# Main_ESP32.net
KiCad netlist of a schematic drawn in EAGLE
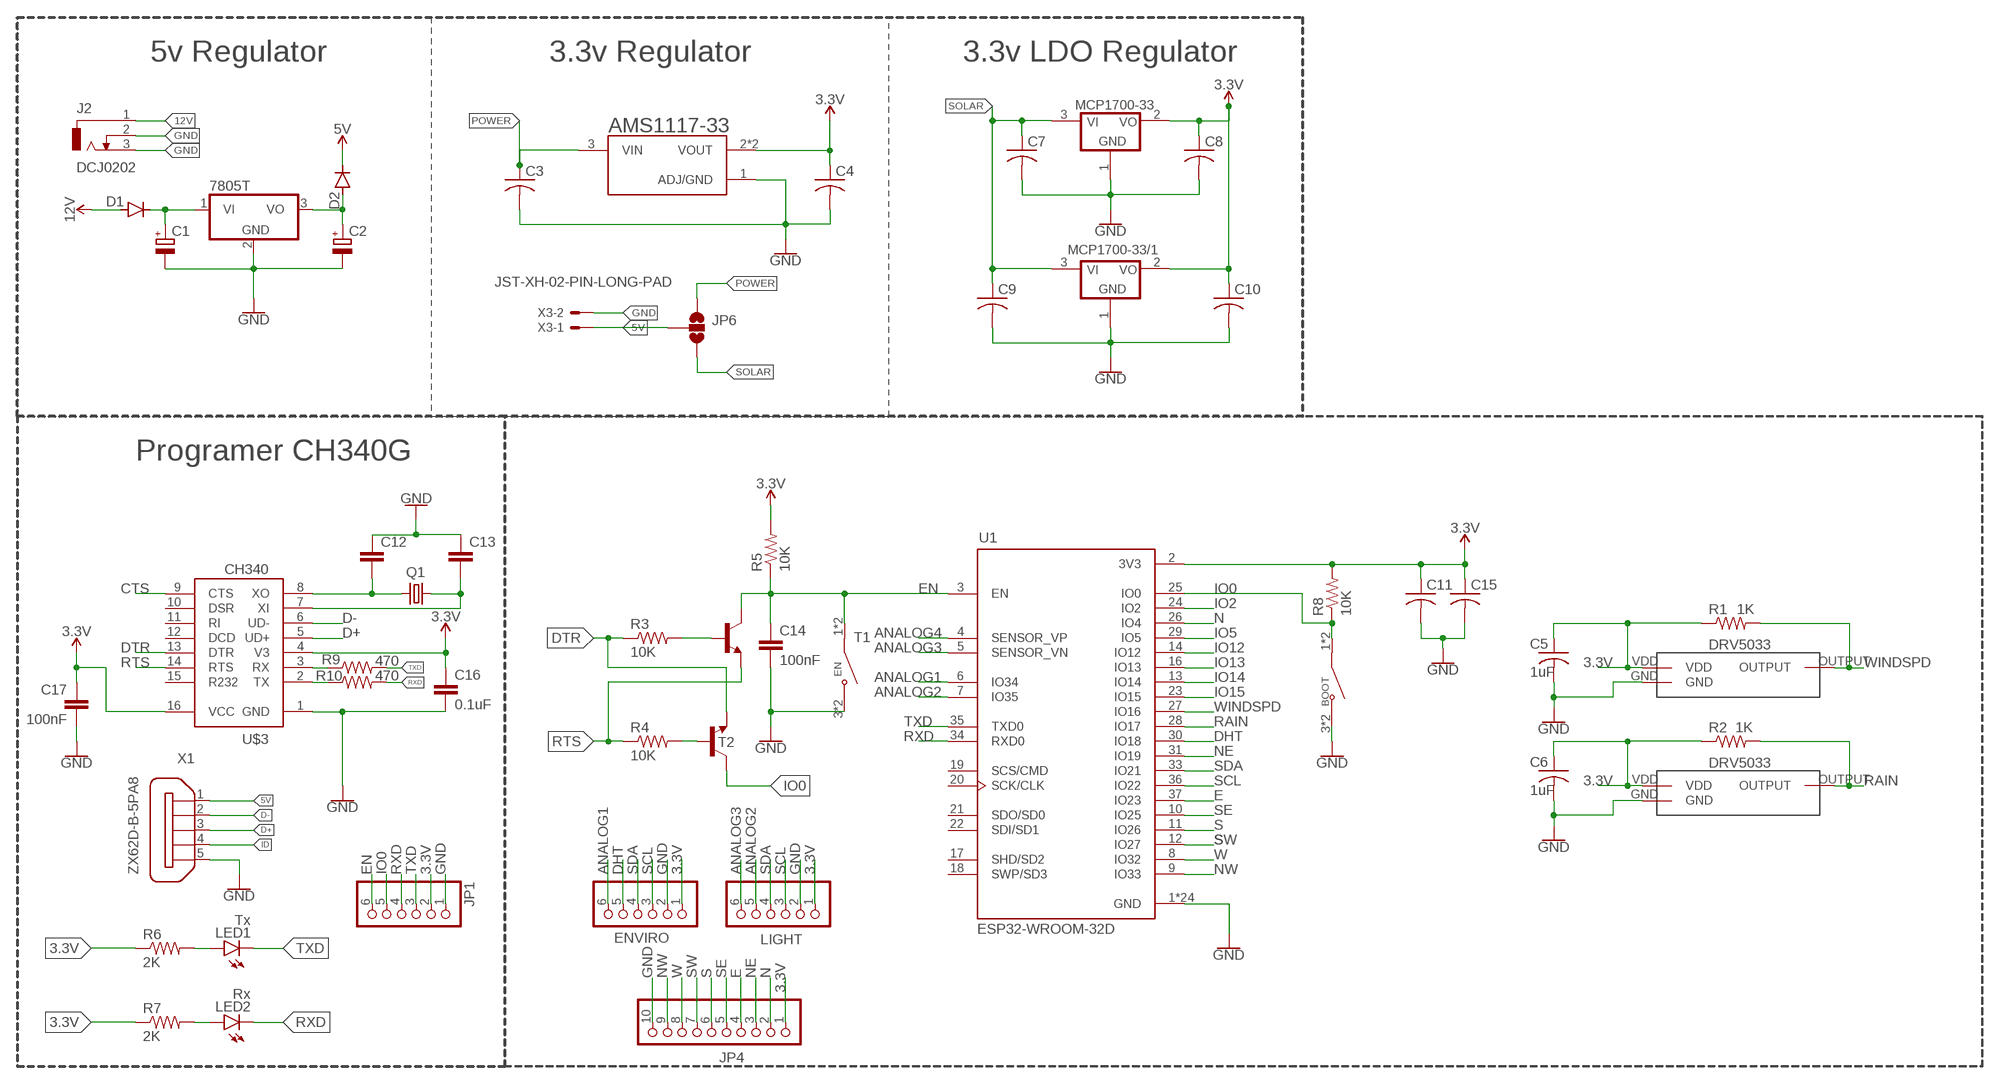
[diagram p0: schematic, sheet 1]

(export (version "E")
  (design (tool "Eeschema 10.0.6"))
  (components
    (comp (ref "AMS1117-33")
      (value "AMS1117-5.0")
      (footprint "eagle-import:SOT229P700X180-4N")
      (fields (field (name "MF") "Advanced Monolithic Systems"))
      (libsource (lib "eagle-import") (part "AMS1117-5.0"))
    )
    (comp (ref "BOOT")
      (value "2-1437565-9")
      (footprint "eagle-import:SW_2-1437565-9")
      (fields (field (name "MF") "TE Connectivity"))
      (libsource (lib "eagle-import") (part "2-1437565-9"))
    )
    (comp (ref "C1")
      (value "CPOL-EUE2.5-5")
      (footprint "eagle-import:E2,5-5")
      (libsource (lib "eagle-import") (part "CPOL-EUE2.5-5"))
    )
    (comp (ref "C2")
      (value "CPOL-EUE2.5-5")
      (footprint "eagle-import:E2,5-5")
      (libsource (lib "eagle-import") (part "CPOL-EUE2.5-5"))
    )
    (comp (ref "C3")
      (value "C-USC1206K")
      (footprint "eagle-import:C1206K")
      (libsource (lib "eagle-import") (part "C-USC1206K"))
    )
    (comp (ref "C4")
      (value "C-USC1206K")
      (footprint "eagle-import:C1206K")
      (libsource (lib "eagle-import") (part "C-USC1206K"))
    )
    (comp (ref "C5")
      (value "1uF")
      (footprint "eagle-import:C1206K")
      (libsource (lib "eagle-import") (part "C-USC1206K"))
    )
    (comp (ref "C6")
      (value "1uF")
      (footprint "eagle-import:C1206K")
      (libsource (lib "eagle-import") (part "C-USC1206K"))
    )
    (comp (ref "C7")
      (value "C-USC1206K")
      (footprint "eagle-import:C1206K")
      (libsource (lib "eagle-import") (part "C-USC1206K"))
    )
    (comp (ref "C8")
      (value "C-USC1206K")
      (footprint "eagle-import:C1206K")
      (libsource (lib "eagle-import") (part "C-USC1206K"))
    )
    (comp (ref "C9")
      (value "C-USC1206K")
      (footprint "eagle-import:C1206K")
      (libsource (lib "eagle-import") (part "C-USC1206K"))
    )
    (comp (ref "C10")
      (value "C-USC1206K")
      (footprint "eagle-import:C1206K")
      (libsource (lib "eagle-import") (part "C-USC1206K"))
    )
    (comp (ref "C11")
      (value "C-USC1206K")
      (footprint "eagle-import:C1206K")
      (libsource (lib "eagle-import") (part "C-USC1206K"))
    )
    (comp (ref "C12")
      (value "C-EUC1206K")
      (footprint "eagle-import:C1206K")
      (libsource (lib "eagle-import") (part "C-EUC1206K"))
    )
    (comp (ref "C13")
      (value "C-EUC1206K")
      (footprint "eagle-import:C1206K")
      (libsource (lib "eagle-import") (part "C-EUC1206K"))
    )
    (comp (ref "C14")
      (value "100nF")
      (footprint "eagle-import:C1206K")
      (libsource (lib "eagle-import") (part "C-EUC1206K"))
    )
    (comp (ref "C15")
      (value "C-USC1206K")
      (footprint "eagle-import:C1206K")
      (libsource (lib "eagle-import") (part "C-USC1206K"))
    )
    (comp (ref "C16")
      (value "0.1uF")
      (footprint "eagle-import:C1206K")
      (libsource (lib "eagle-import") (part "C-EUC1206K"))
    )
    (comp (ref "C17")
      (value "100nF")
      (footprint "eagle-import:C1206K")
      (libsource (lib "eagle-import") (part "C-EUC1206K"))
    )
    (comp (ref "D1")
      (value "1N4148DO35-10")
      (footprint "eagle-import:DO35-10")
      (libsource (lib "eagle-import") (part "1N4148DO35-10"))
    )
    (comp (ref "D2")
      (value "1N4148DO35-10")
      (footprint "eagle-import:DO35-10")
      (libsource (lib "eagle-import") (part "1N4148DO35-10"))
    )
    (comp (ref "EN")
      (value "2-1437565-9")
      (footprint "eagle-import:SW_2-1437565-9")
      (fields (field (name "MF") "TE Connectivity"))
      (libsource (lib "eagle-import") (part "2-1437565-9"))
    )
    (comp (ref "ENVIRO")
      (value "PINHD-1X6/90")
      (footprint "eagle-import:1X06_90")
      (libsource (lib "eagle-import") (part "PINHD-1X6/90"))
    )
    (comp (ref "IC1")
      (value "7805T")
      (footprint "eagle-import:TO220H")
      (libsource (lib "eagle-import") (part "78T05"))
    )
    (comp (ref "J2")
      (value "DCJ0202")
      (footprint "eagle-import:DCJ0202")
      (libsource (lib "eagle-import") (part "DCJ0202"))
    )
    (comp (ref "JP1")
      (value "PINHD-1X6")
      (footprint "eagle-import:1X06")
      (libsource (lib "eagle-import") (part "PINHD-1X6"))
    )
    (comp (ref "JP4")
      (value "PINHD-1X10/90")
      (footprint "eagle-import:1X10_90")
      (libsource (lib "eagle-import") (part "PINHD-1X10/90"))
    )
    (comp (ref "JP6")
      (value "JUMPER-SMT_3_NO_SILK")
      (footprint "eagle-import:SMT-JUMPER_3_NO_SILK")
      (libsource (lib "eagle-import") (part "JUMPER-SMT_3_NO_SILK"))
    )
    (comp (ref "LED1")
      (value "Tx")
      (footprint "eagle-import:CHIPLED_1206")
      (libsource (lib "eagle-import") (part "LEDCHIPLED_1206"))
    )
    (comp (ref "LED2")
      (value "Rx")
      (footprint "eagle-import:CHIPLED_1206")
      (libsource (lib "eagle-import") (part "LEDCHIPLED_1206"))
    )
    (comp (ref "LIGHT")
      (value "Light")
      (footprint "eagle-import:1X06_90")
      (libsource (lib "eagle-import") (part "PINHD-1X6/90"))
    )
    (comp (ref "MCP1700-33")
      (value "MCP1703-3302E/CB")
      (footprint "eagle-import:SOT23A_MICROCHIP_CB")
      (libsource (lib "eagle-import") (part "MCP170302E/CB-33"))
    )
    (comp (ref "MCP1700-33/1")
      (value "MCP1703-3302E/CB")
      (footprint "eagle-import:SOT23A_MICROCHIP_CB")
      (libsource (lib "eagle-import") (part "MCP170302E/CB-33"))
    )
    (comp (ref "Q1")
      (value "CRYSTALHC49S")
      (footprint "eagle-import:HC49_S")
      (libsource (lib "eagle-import") (part "CRYSTALHC49S"))
    )
    (comp (ref "R1")
      (value "1K")
      (footprint "eagle-import:R1206")
      (libsource (lib "eagle-import") (part "R-US_R1206"))
    )
    (comp (ref "R2")
      (value "1K")
      (footprint "eagle-import:R1206")
      (libsource (lib "eagle-import") (part "R-US_R1206"))
    )
    (comp (ref "R3")
      (value "10K")
      (footprint "eagle-import:R1206")
      (libsource (lib "eagle-import") (part "R-US_R1206"))
    )
    (comp (ref "R4")
      (value "10K")
      (footprint "eagle-import:R1206")
      (libsource (lib "eagle-import") (part "R-US_R1206"))
    )
    (comp (ref "R5")
      (value "10K")
      (footprint "eagle-import:R1206")
      (libsource (lib "eagle-import") (part "R-US_R1206"))
    )
    (comp (ref "R6")
      (value "2K")
      (footprint "eagle-import:R1206")
      (libsource (lib "eagle-import") (part "R-US_R1206"))
    )
    (comp (ref "R7")
      (value "2K")
      (footprint "eagle-import:R1206")
      (libsource (lib "eagle-import") (part "R-US_R1206"))
    )
    (comp (ref "R8")
      (value "10K")
      (footprint "eagle-import:R1206")
      (libsource (lib "eagle-import") (part "R-US_R1206"))
    )
    (comp (ref "R9")
      (value "470")
      (footprint "eagle-import:R1206")
      (libsource (lib "eagle-import") (part "R-US_R1206"))
    )
    (comp (ref "R10")
      (value "470")
      (footprint "eagle-import:R1206")
      (libsource (lib "eagle-import") (part "R-US_R1206"))
    )
    (comp (ref "T1")
      (value "BC847")
      (footprint "eagle-import:SOT23")
      (libsource (lib "eagle-import") (part "BC850"))
    )
    (comp (ref "T2")
      (value "BC847")
      (footprint "eagle-import:SOT23")
      (libsource (lib "eagle-import") (part "BC850"))
    )
    (comp (ref "U$1")
      (value "DRV5033")
      (footprint "eagle-import:DRV5033")
      (libsource (lib "eagle-import") (part "DRV5033"))
    )
    (comp (ref "U$2")
      (value "DRV5033")
      (footprint "eagle-import:DRV5033")
      (libsource (lib "eagle-import") (part "DRV5033"))
    )
    (comp (ref "U$3")
      (value "CH340")
      (footprint "eagle-import:SOIC16")
      (fields (field (name "MF") "DFRobot"))
      (libsource (lib "eagle-import") (part "CH340"))
    )
    (comp (ref "U1")
      (value "ESP32-WROOM-32D")
      (footprint "eagle-import:MODULE_ESP32-WROOM-32D")
      (fields (field (name "MF") "Espressif Systems"))
      (libsource (lib "eagle-import") (part "ESP32-WROOM-32D"))
    )
    (comp (ref "X1")
      (value "ZX62D-B-5PA8")
      (footprint "eagle-import:ZX62D-B-5PA8")
      (fields (field (name "MF") "Hirose"))
      (libsource (lib "eagle-import") (part "ZX62D-B-5PA8"))
    )
    (comp (ref "X3")
      (value "JST-XH-02-PIN-LONG-PAD")
      (footprint "eagle-import:JST-XH-02-PACKAGE-LONG-PAD")
      (libsource (lib "eagle-import") (part "JST-XH-02-PIN-LONG-PAD"))
    )
  )
  (nets
    (net (code "1") (name "/ANALOG1") (class "Default")
      (node (ref "ENVIRO") (pin "6") (pinfunction "6_6") (pintype "passive"))
      (node (ref "U1") (pin "6") (pinfunction "IO34_6") (pintype "input"))
    )
    (net (code "2") (name "/ANALOG2") (class "Default")
      (node (ref "LIGHT") (pin "5") (pinfunction "5_5") (pintype "passive"))
      (node (ref "U1") (pin "7") (pinfunction "IO35_7") (pintype "input"))
    )
    (net (code "3") (name "/ANALOG3") (class "Default")
      (node (ref "LIGHT") (pin "6") (pinfunction "6_6") (pintype "passive"))
      (node (ref "U1") (pin "5") (pinfunction "SENSOR_VN_5") (pintype "input"))
    )
    (net (code "4") (name "/ANALOG4") (class "Default")
      (node (ref "U1") (pin "4") (pinfunction "SENSOR_VP_4") (pintype "input"))
    )
    (net (code "5") (name "/CTS") (class "Default")
      (node (ref "U$3") (pin "9") (pinfunction "CTS_9") (pintype "bidirectional"))
    )
    (net (code "6") (name "/DHT") (class "Default")
      (node (ref "ENVIRO") (pin "5") (pinfunction "5_5") (pintype "passive"))
      (node (ref "U1") (pin "30") (pinfunction "IO18_30") (pintype "bidirectional"))
    )
    (net (code "7") (name "/E") (class "Default")
      (node (ref "JP4") (pin "4") (pinfunction "4_4") (pintype "passive"))
      (node (ref "U1") (pin "37") (pinfunction "IO23_37") (pintype "bidirectional"))
    )
    (net (code "8") (name "/EN") (class "Default")
      (node (ref "C14") (pin "1") (pinfunction "1_1") (pintype "passive"))
      (node (ref "EN") (pin "1") (pinfunction "COM_1") (pintype "passive"))
      (node (ref "EN") (pin "2") (pinfunction "COM_2") (pintype "passive"))
      (node (ref "JP1") (pin "6") (pinfunction "6_6") (pintype "passive"))
      (node (ref "R5") (pin "1") (pinfunction "1_1") (pintype "passive"))
      (node (ref "T1") (pin "3") (pinfunction "C_3") (pintype "passive"))
      (node (ref "U1") (pin "3") (pinfunction "EN_3") (pintype "input"))
    )
    (net (code "9") (name "/IO2") (class "Default")
      (node (ref "U1") (pin "24") (pinfunction "IO2_24") (pintype "bidirectional"))
    )
    (net (code "10") (name "/IO5") (class "Default")
      (node (ref "U1") (pin "29") (pinfunction "IO5_29") (pintype "bidirectional"))
    )
    (net (code "11") (name "/IO12") (class "Default")
      (node (ref "U1") (pin "14") (pinfunction "IO12_14") (pintype "bidirectional"))
    )
    (net (code "12") (name "/IO13") (class "Default")
      (node (ref "U1") (pin "16") (pinfunction "IO13_16") (pintype "bidirectional"))
    )
    (net (code "13") (name "/IO14") (class "Default")
      (node (ref "U1") (pin "13") (pinfunction "IO14_13") (pintype "bidirectional"))
    )
    (net (code "14") (name "/IO15") (class "Default")
      (node (ref "U1") (pin "23") (pinfunction "IO15_23") (pintype "bidirectional"))
    )
    (net (code "15") (name "/N") (class "Default")
      (node (ref "JP4") (pin "2") (pinfunction "2_2") (pintype "passive"))
      (node (ref "U1") (pin "26") (pinfunction "IO4_26") (pintype "bidirectional"))
    )
    (net (code "16") (name "/NE") (class "Default")
      (node (ref "JP4") (pin "3") (pinfunction "3_3") (pintype "passive"))
      (node (ref "U1") (pin "31") (pinfunction "IO19_31") (pintype "bidirectional"))
    )
    (net (code "17") (name "/NW") (class "Default")
      (node (ref "JP4") (pin "9") (pinfunction "9_9") (pintype "passive"))
      (node (ref "U1") (pin "9") (pinfunction "IO33_9") (pintype "bidirectional"))
    )
    (net (code "18") (name "/RAIN") (class "Default")
      (node (ref "R2") (pin "2") (pinfunction "2_2") (pintype "passive"))
      (node (ref "U$1") (pin "OUTPUT") (pinfunction "OUTPUT_OUTPUT") (pintype "bidirectional"))
      (node (ref "U1") (pin "28") (pinfunction "IO17_28") (pintype "bidirectional"))
    )
    (net (code "19") (name "/S") (class "Default")
      (node (ref "JP4") (pin "6") (pinfunction "6_6") (pintype "passive"))
      (node (ref "U1") (pin "11") (pinfunction "IO26_11") (pintype "bidirectional"))
    )
    (net (code "20") (name "/SCL") (class "Default")
      (node (ref "ENVIRO") (pin "3") (pinfunction "3_3") (pintype "passive"))
      (node (ref "LIGHT") (pin "3") (pinfunction "3_3") (pintype "passive"))
      (node (ref "U1") (pin "36") (pinfunction "IO22_36") (pintype "bidirectional"))
    )
    (net (code "21") (name "/SDA") (class "Default")
      (node (ref "ENVIRO") (pin "4") (pinfunction "4_4") (pintype "passive"))
      (node (ref "LIGHT") (pin "4") (pinfunction "4_4") (pintype "passive"))
      (node (ref "U1") (pin "33") (pinfunction "IO21_33") (pintype "bidirectional"))
    )
    (net (code "22") (name "/SE") (class "Default")
      (node (ref "JP4") (pin "5") (pinfunction "5_5") (pintype "passive"))
      (node (ref "U1") (pin "10") (pinfunction "IO25_10") (pintype "bidirectional"))
    )
    (net (code "23") (name "/SW") (class "Default")
      (node (ref "JP4") (pin "7") (pinfunction "7_7") (pintype "passive"))
      (node (ref "U1") (pin "12") (pinfunction "IO27_12") (pintype "bidirectional"))
    )
    (net (code "24") (name "/W") (class "Default")
      (node (ref "JP4") (pin "8") (pinfunction "8_8") (pintype "passive"))
      (node (ref "U1") (pin "8") (pinfunction "IO32_8") (pintype "bidirectional"))
    )
    (net (code "25") (name "/WINDSPD") (class "Default")
      (node (ref "R1") (pin "2") (pinfunction "2_2") (pintype "passive"))
      (node (ref "U$2") (pin "OUTPUT") (pinfunction "OUTPUT_OUTPUT") (pintype "bidirectional"))
      (node (ref "U1") (pin "27") (pinfunction "IO16_27") (pintype "bidirectional"))
    )
    (net (code "26") (name "3.3V") (class "Default")
      (node (ref "AMS1117-33") (pin "2") (pinfunction "VOUT_2") (pintype "output"))
      (node (ref "AMS1117-33") (pin "4") (pinfunction "VOUT_4") (pintype "output"))
      (node (ref "C10") (pin "1") (pinfunction "1_1") (pintype "passive"))
      (node (ref "C11") (pin "1") (pinfunction "1_1") (pintype "passive"))
      (node (ref "C15") (pin "1") (pinfunction "1_1") (pintype "passive"))
      (node (ref "C16") (pin "1") (pinfunction "1_1") (pintype "passive"))
      (node (ref "C17") (pin "1") (pinfunction "1_1") (pintype "passive"))
      (node (ref "C4") (pin "1") (pinfunction "1_1") (pintype "passive"))
      (node (ref "C5") (pin "1") (pinfunction "1_1") (pintype "passive"))
      (node (ref "C6") (pin "1") (pinfunction "1_1") (pintype "passive"))
      (node (ref "C8") (pin "1") (pinfunction "1_1") (pintype "passive"))
      (node (ref "ENVIRO") (pin "1") (pinfunction "1_1") (pintype "passive"))
      (node (ref "JP1") (pin "2") (pinfunction "2_2") (pintype "passive"))
      (node (ref "JP4") (pin "1") (pinfunction "1_1") (pintype "passive"))
      (node (ref "LIGHT") (pin "1") (pinfunction "1_1") (pintype "passive"))
      (node (ref "MCP1700-33") (pin "2") (pinfunction "VO_2") (pintype "passive"))
      (node (ref "MCP1700-33/1") (pin "2") (pinfunction "VO_2") (pintype "passive"))
      (node (ref "R1") (pin "1") (pinfunction "1_1") (pintype "passive"))
      (node (ref "R2") (pin "1") (pinfunction "1_1") (pintype "passive"))
      (node (ref "R5") (pin "2") (pinfunction "2_2") (pintype "passive"))
      (node (ref "R6") (pin "1") (pinfunction "1_1") (pintype "passive"))
      (node (ref "R7") (pin "1") (pinfunction "1_1") (pintype "passive"))
      (node (ref "R8") (pin "2") (pinfunction "2_2") (pintype "passive"))
      (node (ref "U$1") (pin "VDD") (pinfunction "VDD_VDD") (pintype "bidirectional"))
      (node (ref "U$2") (pin "VDD") (pinfunction "VDD_VDD") (pintype "bidirectional"))
      (node (ref "U$3") (pin "16") (pinfunction "VCC_16") (pintype "power_in"))
      (node (ref "U$3") (pin "4") (pinfunction "V3_4") (pintype "power_in"))
      (node (ref "U1") (pin "2") (pinfunction "3V3_2") (pintype "power_in"))
    )
    (net (code "27") (name "5V") (class "Default")
      (node (ref "D2") (pin "C") (pinfunction "C_C") (pintype "passive"))
      (node (ref "JP6") (pin "2") (pinfunction "2_2") (pintype "passive"))
      (node (ref "X1") (pin "1") (pinfunction "1_1") (pintype "passive"))
      (node (ref "X3") (pin "1") (pinfunction "S_1") (pintype "passive"))
    )
    (net (code "28") (name "12V") (class "Default")
      (node (ref "D1") (pin "A") (pinfunction "A_A") (pintype "passive"))
      (node (ref "J2") (pin "1") (pinfunction "1_1") (pintype "passive"))
    )
    (net (code "29") (name "D+") (class "Default")
      (node (ref "U$3") (pin "5") (pinfunction "UD+_5") (pintype "bidirectional"))
      (node (ref "X1") (pin "3") (pinfunction "3_3") (pintype "passive"))
    )
    (net (code "30") (name "D-") (class "Default")
      (node (ref "U$3") (pin "6") (pinfunction "UD-_6") (pintype "bidirectional"))
      (node (ref "X1") (pin "2") (pinfunction "2_2") (pintype "passive"))
    )
    (net (code "31") (name "DTR") (class "Default")
      (node (ref "R3") (pin "1") (pinfunction "1_1") (pintype "passive"))
      (node (ref "T2") (pin "2") (pinfunction "E_2") (pintype "passive"))
      (node (ref "U$3") (pin "13") (pinfunction "DTR_13") (pintype "bidirectional"))
    )
    (net (code "32") (name "GND") (class "Default")
      (node (ref "AMS1117-33") (pin "1") (pinfunction "ADJ/GND_1") (pintype "power_in"))
      (node (ref "BOOT") (pin "3") (pinfunction "NO_3") (pintype "passive"))
      (node (ref "BOOT") (pin "4") (pinfunction "NO_4") (pintype "passive"))
      (node (ref "C1") (pin "-") (pinfunction "-_-") (pintype "passive"))
      (node (ref "C10") (pin "2") (pinfunction "2_2") (pintype "passive"))
      (node (ref "C11") (pin "2") (pinfunction "2_2") (pintype "passive"))
      (node (ref "C12") (pin "1") (pinfunction "1_1") (pintype "passive"))
      (node (ref "C13") (pin "1") (pinfunction "1_1") (pintype "passive"))
      (node (ref "C14") (pin "2") (pinfunction "2_2") (pintype "passive"))
      (node (ref "C15") (pin "2") (pinfunction "2_2") (pintype "passive"))
      (node (ref "C16") (pin "2") (pinfunction "2_2") (pintype "passive"))
      (node (ref "C17") (pin "2") (pinfunction "2_2") (pintype "passive"))
      (node (ref "C2") (pin "-") (pinfunction "-_-") (pintype "passive"))
      (node (ref "C3") (pin "2") (pinfunction "2_2") (pintype "passive"))
      (node (ref "C4") (pin "2") (pinfunction "2_2") (pintype "passive"))
      (node (ref "C5") (pin "2") (pinfunction "2_2") (pintype "passive"))
      (node (ref "C6") (pin "2") (pinfunction "2_2") (pintype "passive"))
      (node (ref "C7") (pin "2") (pinfunction "2_2") (pintype "passive"))
      (node (ref "C8") (pin "2") (pinfunction "2_2") (pintype "passive"))
      (node (ref "C9") (pin "2") (pinfunction "2_2") (pintype "passive"))
      (node (ref "EN") (pin "3") (pinfunction "NO_3") (pintype "passive"))
      (node (ref "EN") (pin "4") (pinfunction "NO_4") (pintype "passive"))
      (node (ref "ENVIRO") (pin "2") (pinfunction "2_2") (pintype "passive"))
      (node (ref "IC1") (pin "2") (pinfunction "GND_2") (pintype "passive"))
      (node (ref "J2") (pin "2") (pinfunction "2_2") (pintype "passive"))
      (node (ref "J2") (pin "3") (pinfunction "3_3") (pintype "passive"))
      (node (ref "JP1") (pin "1") (pinfunction "1_1") (pintype "passive"))
      (node (ref "JP4") (pin "10") (pinfunction "10_10") (pintype "passive"))
      (node (ref "LIGHT") (pin "2") (pinfunction "2_2") (pintype "passive"))
      (node (ref "MCP1700-33") (pin "1") (pinfunction "GND_1") (pintype "power_in"))
      (node (ref "MCP1700-33/1") (pin "1") (pinfunction "GND_1") (pintype "power_in"))
      (node (ref "U$1") (pin "GND") (pinfunction "GND_GND") (pintype "bidirectional"))
      (node (ref "U$2") (pin "GND") (pinfunction "GND_GND") (pintype "bidirectional"))
      (node (ref "U$3") (pin "1") (pinfunction "GND_1") (pintype "power_in"))
      (node (ref "U1") (pin "1") (pinfunction "GND_1") (pintype "power_in"))
      (node (ref "U1") (pin "15") (pinfunction "GND_15") (pintype "power_in"))
      (node (ref "U1") (pin "38") (pinfunction "GND_38") (pintype "power_in"))
      (node (ref "U1") (pin "39_1") (pinfunction "GND_39_1") (pintype "power_in"))
      (node (ref "U1") (pin "39_10") (pinfunction "GND_39_10") (pintype "power_in"))
      (node (ref "U1") (pin "39_11") (pinfunction "GND_39_11") (pintype "power_in"))
      (node (ref "U1") (pin "39_12") (pinfunction "GND_39_12") (pintype "power_in"))
      (node (ref "U1") (pin "39_13") (pinfunction "GND_39_13") (pintype "power_in"))
      (node (ref "U1") (pin "39_14") (pinfunction "GND_39_14") (pintype "power_in"))
      (node (ref "U1") (pin "39_15") (pinfunction "GND_39_15") (pintype "power_in"))
      (node (ref "U1") (pin "39_16") (pinfunction "GND_39_16") (pintype "power_in"))
      (node (ref "U1") (pin "39_17") (pinfunction "GND_39_17") (pintype "power_in"))
      (node (ref "U1") (pin "39_18") (pinfunction "GND_39_18") (pintype "power_in"))
      (node (ref "U1") (pin "39_19") (pinfunction "GND_39_19") (pintype "power_in"))
      (node (ref "U1") (pin "39_2") (pinfunction "GND_39_2") (pintype "power_in"))
      (node (ref "U1") (pin "39_20") (pinfunction "GND_39_20") (pintype "power_in"))
      (node (ref "U1") (pin "39_21") (pinfunction "GND_39_21") (pintype "power_in"))
      (node (ref "U1") (pin "39_3") (pinfunction "GND_39_3") (pintype "power_in"))
      (node (ref "U1") (pin "39_4") (pinfunction "GND_39_4") (pintype "power_in"))
      (node (ref "U1") (pin "39_5") (pinfunction "GND_39_5") (pintype "power_in"))
      (node (ref "U1") (pin "39_6") (pinfunction "GND_39_6") (pintype "power_in"))
      (node (ref "U1") (pin "39_7") (pinfunction "GND_39_7") (pintype "power_in"))
      (node (ref "U1") (pin "39_8") (pinfunction "GND_39_8") (pintype "power_in"))
      (node (ref "U1") (pin "39_9") (pinfunction "GND_39_9") (pintype "power_in"))
      (node (ref "X1") (pin "5") (pinfunction "5_5") (pintype "passive"))
      (node (ref "X3") (pin "2") (pinfunction "S_2") (pintype "passive"))
    )
    (net (code "33") (name "ID") (class "Default")
      (node (ref "X1") (pin "4") (pinfunction "4_4") (pintype "passive"))
    )
    (net (code "34") (name "IO0") (class "Default")
      (node (ref "BOOT") (pin "1") (pinfunction "COM_1") (pintype "passive"))
      (node (ref "BOOT") (pin "2") (pinfunction "COM_2") (pintype "passive"))
      (node (ref "JP1") (pin "5") (pinfunction "5_5") (pintype "passive"))
      (node (ref "R8") (pin "1") (pinfunction "1_1") (pintype "passive"))
      (node (ref "T2") (pin "3") (pinfunction "C_3") (pintype "passive"))
      (node (ref "U1") (pin "25") (pinfunction "IO0_25") (pintype "bidirectional"))
    )
    (net (code "35") (name "Net-(IC1-VI)") (class "Default")
      (node (ref "C1") (pin "+") (pinfunction "+_+") (pintype "passive"))
      (node (ref "D1") (pin "C") (pinfunction "C_C") (pintype "passive"))
      (node (ref "IC1") (pin "1") (pinfunction "VI_1") (pintype "input"))
    )
    (net (code "36") (name "Net-(IC1-VO)") (class "Default")
      (node (ref "C2") (pin "+") (pinfunction "+_+") (pintype "passive"))
      (node (ref "D2") (pin "A") (pinfunction "A_A") (pintype "passive"))
      (node (ref "IC1") (pin "3") (pinfunction "VO_3") (pintype "passive"))
    )
    (net (code "37") (name "Net-(LED1-PadA)") (class "Default")
      (node (ref "LED1") (pin "A") (pinfunction "A_A") (pintype "passive"))
      (node (ref "R6") (pin "2") (pinfunction "2_2") (pintype "passive"))
    )
    (net (code "38") (name "Net-(LED2-PadA)") (class "Default")
      (node (ref "LED2") (pin "A") (pinfunction "A_A") (pintype "passive"))
      (node (ref "R7") (pin "2") (pinfunction "2_2") (pintype "passive"))
    )
    (net (code "39") (name "Net-(T1-B)") (class "Default")
      (node (ref "R3") (pin "2") (pinfunction "2_2") (pintype "passive"))
      (node (ref "T1") (pin "1") (pinfunction "B_1") (pintype "passive"))
    )
    (net (code "40") (name "Net-(T2-B)") (class "Default")
      (node (ref "R4") (pin "2") (pinfunction "2_2") (pintype "passive"))
      (node (ref "T2") (pin "1") (pinfunction "B_1") (pintype "passive"))
    )
    (net (code "41") (name "Net-(U$3-RX)") (class "Default")
      (node (ref "R9") (pin "1") (pinfunction "1_1") (pintype "passive"))
      (node (ref "U$3") (pin "3") (pinfunction "RX_3") (pintype "input"))
    )
    (net (code "42") (name "Net-(U$3-TX)") (class "Default")
      (node (ref "R10") (pin "1") (pinfunction "1_1") (pintype "passive"))
      (node (ref "U$3") (pin "2") (pinfunction "TX_2") (pintype "output"))
    )
    (net (code "43") (name "Net-(U$3-XI)") (class "Default")
      (node (ref "C13") (pin "2") (pinfunction "2_2") (pintype "passive"))
      (node (ref "Q1") (pin "1") (pinfunction "1_1") (pintype "passive"))
      (node (ref "U$3") (pin "7") (pinfunction "XI_7") (pintype "input"))
    )
    (net (code "44") (name "Net-(U$3-XO)") (class "Default")
      (node (ref "C12") (pin "2") (pinfunction "2_2") (pintype "passive"))
      (node (ref "Q1") (pin "2") (pinfunction "2_2") (pintype "passive"))
      (node (ref "U$3") (pin "8") (pinfunction "XO_8") (pintype "output"))
    )
    (net (code "45") (name "POWER") (class "Default")
      (node (ref "AMS1117-33") (pin "3") (pinfunction "VIN_3") (pintype "input"))
      (node (ref "C3") (pin "1") (pinfunction "1_1") (pintype "passive"))
      (node (ref "JP6") (pin "1") (pinfunction "1_1") (pintype "passive"))
    )
    (net (code "46") (name "RTS") (class "Default")
      (node (ref "R4") (pin "1") (pinfunction "1_1") (pintype "passive"))
      (node (ref "T1") (pin "2") (pinfunction "E_2") (pintype "passive"))
      (node (ref "U$3") (pin "14") (pinfunction "RTS_14") (pintype "bidirectional"))
    )
    (net (code "47") (name "RXD") (class "Default")
      (node (ref "JP1") (pin "4") (pinfunction "4_4") (pintype "passive"))
      (node (ref "LED2") (pin "C") (pinfunction "C_C") (pintype "passive"))
      (node (ref "R10") (pin "2") (pinfunction "2_2") (pintype "passive"))
      (node (ref "U1") (pin "34") (pinfunction "RXD0_34") (pintype "bidirectional"))
    )
    (net (code "48") (name "SOLAR") (class "Default")
      (node (ref "C7") (pin "1") (pinfunction "1_1") (pintype "passive"))
      (node (ref "C9") (pin "1") (pinfunction "1_1") (pintype "passive"))
      (node (ref "JP6") (pin "3") (pinfunction "3_3") (pintype "passive"))
      (node (ref "MCP1700-33") (pin "3") (pinfunction "VI_3") (pintype "power_in"))
      (node (ref "MCP1700-33/1") (pin "3") (pinfunction "VI_3") (pintype "power_in"))
    )
    (net (code "49") (name "TXD") (class "Default")
      (node (ref "JP1") (pin "3") (pinfunction "3_3") (pintype "passive"))
      (node (ref "LED1") (pin "C") (pinfunction "C_C") (pintype "passive"))
      (node (ref "R9") (pin "2") (pinfunction "2_2") (pintype "passive"))
      (node (ref "U1") (pin "35") (pinfunction "TXD0_35") (pintype "bidirectional"))
    )
    (net (code "50") (name "unconnected-(U$3-DCD-Pad12)") (class "Default")
      (node (ref "U$3") (pin "12") (pinfunction "DCD_12") (pintype "bidirectional"))
    )
    (net (code "51") (name "unconnected-(U$3-DSR-Pad10)") (class "Default")
      (node (ref "U$3") (pin "10") (pinfunction "DSR_10") (pintype "bidirectional"))
    )
    (net (code "52") (name "unconnected-(U$3-R232-Pad15)") (class "Default")
      (node (ref "U$3") (pin "15") (pinfunction "R232_15") (pintype "bidirectional"))
    )
    (net (code "53") (name "unconnected-(U$3-RI-Pad11)") (class "Default")
      (node (ref "U$3") (pin "11") (pinfunction "RI_11") (pintype "bidirectional"))
    )
    (net (code "54") (name "unconnected-(U1-SCK{slash}CLK-Pad20)") (class "Default")
      (node (ref "U1") (pin "20") (pinfunction "SCK/CLK_20") (pintype "bidirectional"))
    )
    (net (code "55") (name "unconnected-(U1-SCS{slash}CMD-Pad19)") (class "Default")
      (node (ref "U1") (pin "19") (pinfunction "SCS/CMD_19") (pintype "bidirectional"))
    )
    (net (code "56") (name "unconnected-(U1-SDI{slash}SD1-Pad22)") (class "Default")
      (node (ref "U1") (pin "22") (pinfunction "SDI/SD1_22") (pintype "bidirectional"))
    )
    (net (code "57") (name "unconnected-(U1-SDO{slash}SD0-Pad21)") (class "Default")
      (node (ref "U1") (pin "21") (pinfunction "SDO/SD0_21") (pintype "bidirectional"))
    )
    (net (code "58") (name "unconnected-(U1-SHD{slash}SD2-Pad17)") (class "Default")
      (node (ref "U1") (pin "17") (pinfunction "SHD/SD2_17") (pintype "bidirectional"))
    )
    (net (code "59") (name "unconnected-(U1-SWP{slash}SD3-Pad18)") (class "Default")
      (node (ref "U1") (pin "18") (pinfunction "SWP/SD3_18") (pintype "bidirectional"))
    )
  )
)
